# Shifter.net
KiCad netlist of a schematic drawn in Altium Designer
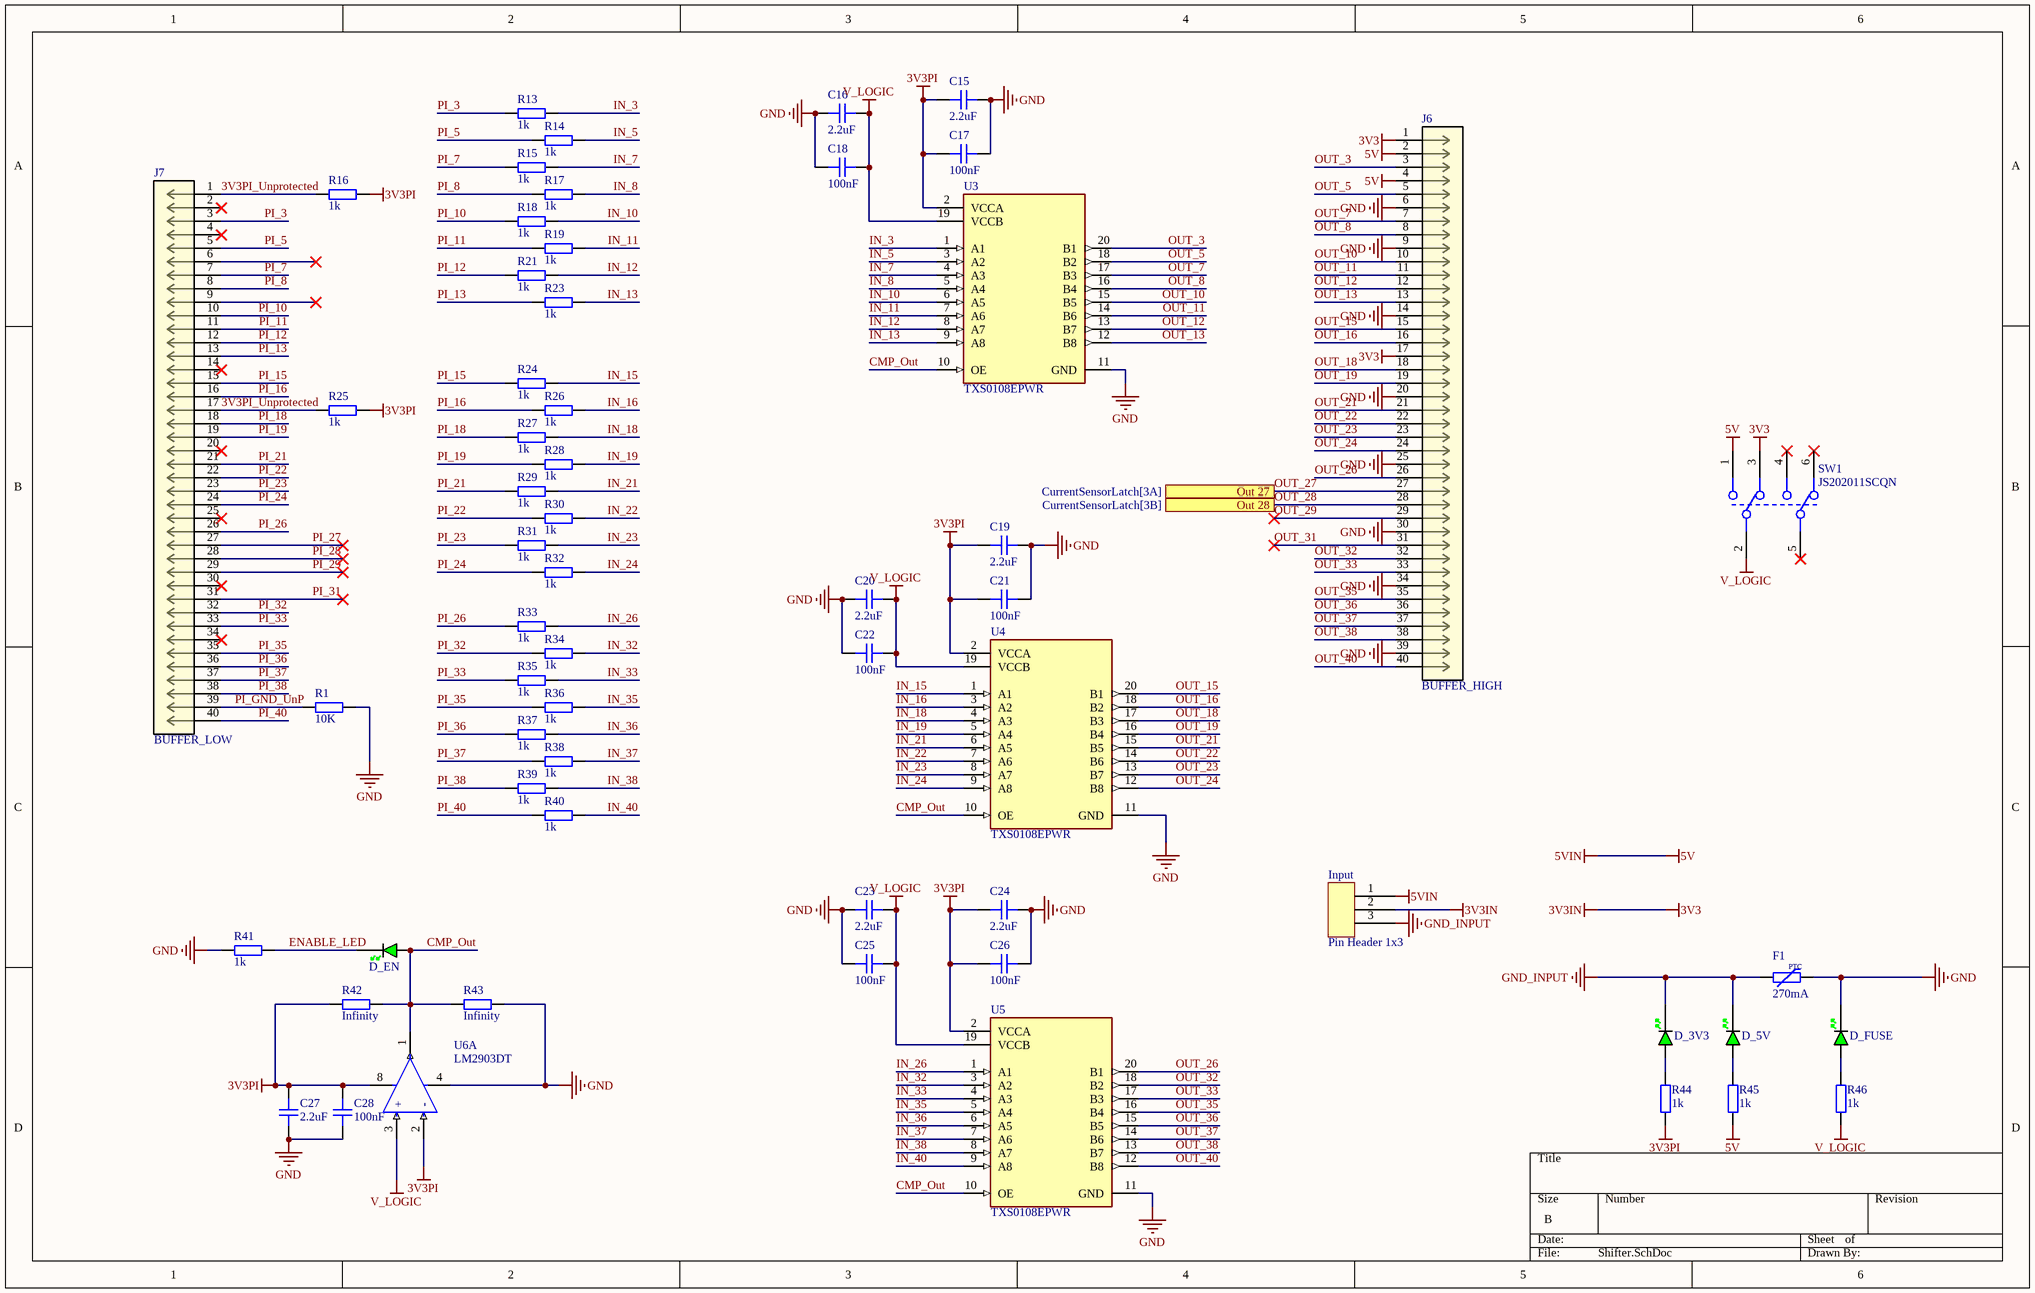
[diagram p0: Shifter.SchDoc]

(export (version "E")
  (design (tool "Eeschema 10.0.6"))
  (components
    (comp (ref "C15")
      (value "2.2uF")
      (footprint "CAP_0805")
      (description "Capacitor SMD 0805 16V")
      (libsource (lib "Schematic-Lib-PhilsLab") (part "CAP_0805_16V"))
    )
    (comp (ref "C16")
      (value "2.2uF")
      (footprint "CAP_0805")
      (description "Capacitor SMD 0805 16V")
      (libsource (lib "Schematic-Lib-PhilsLab") (part "CAP_0805_16V"))
    )
    (comp (ref "C17")
      (value "100nF")
      (footprint "CAP_0805")
      (description "Capacitor SMD 0805 16V")
      (libsource (lib "Schematic-Lib-PhilsLab") (part "CAP_0805_16V"))
    )
    (comp (ref "C18")
      (value "100nF")
      (footprint "CAP_0805")
      (description "Capacitor SMD 0805 16V")
      (libsource (lib "Schematic-Lib-PhilsLab") (part "CAP_0805_16V"))
    )
    (comp (ref "C19")
      (value "2.2uF")
      (footprint "CAP_0805")
      (description "Capacitor SMD 0805 16V")
      (libsource (lib "Schematic-Lib-PhilsLab") (part "CAP_0805_16V"))
    )
    (comp (ref "C20")
      (value "2.2uF")
      (footprint "CAP_0805")
      (description "Capacitor SMD 0805 16V")
      (libsource (lib "Schematic-Lib-PhilsLab") (part "CAP_0805_16V"))
    )
    (comp (ref "C21")
      (value "100nF")
      (footprint "CAP_0805")
      (description "Capacitor SMD 0805 16V")
      (libsource (lib "Schematic-Lib-PhilsLab") (part "CAP_0805_16V"))
    )
    (comp (ref "C22")
      (value "100nF")
      (footprint "CAP_0805")
      (description "Capacitor SMD 0805 16V")
      (libsource (lib "Schematic-Lib-PhilsLab") (part "CAP_0805_16V"))
    )
    (comp (ref "C23")
      (value "2.2uF")
      (footprint "CAP_0805")
      (description "Capacitor SMD 0805 16V")
      (libsource (lib "Schematic-Lib-PhilsLab") (part "CAP_0805_16V"))
    )
    (comp (ref "C24")
      (value "2.2uF")
      (footprint "CAP_0805")
      (description "Capacitor SMD 0805 16V")
      (libsource (lib "Schematic-Lib-PhilsLab") (part "CAP_0805_16V"))
    )
    (comp (ref "C25")
      (value "100nF")
      (footprint "CAP_0805")
      (description "Capacitor SMD 0805 16V")
      (libsource (lib "Schematic-Lib-PhilsLab") (part "CAP_0805_16V"))
    )
    (comp (ref "C26")
      (value "100nF")
      (footprint "CAP_0805")
      (description "Capacitor SMD 0805 16V")
      (libsource (lib "Schematic-Lib-PhilsLab") (part "CAP_0805_16V"))
    )
    (comp (ref "C27")
      (value "2.2uF")
      (footprint "CAP_0805")
      (description "Capacitor SMD 0805 16V")
      (libsource (lib "Schematic-Lib-PhilsLab") (part "CAP_0805_16V"))
    )
    (comp (ref "C28")
      (value "100nF")
      (footprint "CAP_0805")
      (description "Capacitor SMD 0805 16V")
      (libsource (lib "Schematic-Lib-PhilsLab") (part "CAP_0805_16V"))
    )
    (comp (ref "D_3V3")
      (value "GREEN")
      (footprint "LED_0603_GREEN")
      (description "LED 0603 GREEN SMD")
      (libsource (lib "Schematic-Lib-PhilsLab") (part "LED_0603_GREEN"))
    )
    (comp (ref "D_5V")
      (value "GREEN")
      (footprint "LED_0603_GREEN")
      (description "LED 0603 GREEN SMD")
      (libsource (lib "Schematic-Lib-PhilsLab") (part "LED_0603_GREEN"))
    )
    (comp (ref "D_EN")
      (value "GREEN")
      (footprint "LED_0603_GREEN")
      (description "LED 0603 GREEN SMD")
      (libsource (lib "Schematic-Lib-PhilsLab") (part "LED_0603_GREEN"))
    )
    (comp (ref "D_FUSE")
      (value "GREEN")
      (footprint "LED_0603_GREEN")
      (description "LED 0603 GREEN SMD")
      (libsource (lib "Schematic-Lib-PhilsLab") (part "LED_0603_GREEN"))
    )
    (comp (ref "F1")
      (value "270mA")
      (footprint "FUSE_1206")
      (description "Fuse PPTC SMD 1206\r\nSMD1206B010TF")
      (libsource (lib "Schematic-Lib-PhilsLab") (part "FUSE_PPTC_1206"))
    )
    (comp (ref "Input")
      (value "Pin Header 1x3")
      (footprint "Pin Header 1x3")
      (description ".1\" pitch pin header")
      (libsource (lib "TomDownesLibray") (part "Pin Header 1x3"))
    )
    (comp (ref "J6")
      (value "BUFFER_HIGH")
      (footprint "CONN_3020-40-0100-00_CNC")
      (description "No Description Available")
      (libsource (lib "3020-40-0100-00") (part "3020-40-0100-00"))
    )
    (comp (ref "J7")
      (value "BUFFER_LOW")
      (footprint "CONN_3020-40-0100-00_CNC")
      (description "No Description Available")
      (libsource (lib "3020-40-0100-00") (part "3020-40-0100-00"))
    )
    (comp (ref "R1")
      (value "10K")
      (footprint "RES_0603")
      (description "Resistor SMD 0603")
      (libsource (lib "Schematic-Lib-PhilsLab") (part "RES_0603"))
    )
    (comp (ref "R13")
      (value "1k")
      (footprint "RES_0603")
      (description "Resistor SMD 0603")
      (libsource (lib "Schematic-Lib-PhilsLab") (part "RES_0603"))
    )
    (comp (ref "R14")
      (value "1k")
      (footprint "RES_0603")
      (description "Resistor SMD 0603")
      (libsource (lib "Schematic-Lib-PhilsLab") (part "RES_0603"))
    )
    (comp (ref "R15")
      (value "1k")
      (footprint "RES_0603")
      (description "Resistor SMD 0603")
      (libsource (lib "Schematic-Lib-PhilsLab") (part "RES_0603"))
    )
    (comp (ref "R16")
      (value "1k")
      (footprint "RES_0603")
      (description "Resistor SMD 0603")
      (libsource (lib "Schematic-Lib-PhilsLab") (part "RES_0603"))
    )
    (comp (ref "R17")
      (value "1k")
      (footprint "RES_0603")
      (description "Resistor SMD 0603")
      (libsource (lib "Schematic-Lib-PhilsLab") (part "RES_0603"))
    )
    (comp (ref "R18")
      (value "1k")
      (footprint "RES_0603")
      (description "Resistor SMD 0603")
      (libsource (lib "Schematic-Lib-PhilsLab") (part "RES_0603"))
    )
    (comp (ref "R19")
      (value "1k")
      (footprint "RES_0603")
      (description "Resistor SMD 0603")
      (libsource (lib "Schematic-Lib-PhilsLab") (part "RES_0603"))
    )
    (comp (ref "R21")
      (value "1k")
      (footprint "RES_0603")
      (description "Resistor SMD 0603")
      (libsource (lib "Schematic-Lib-PhilsLab") (part "RES_0603"))
    )
    (comp (ref "R23")
      (value "1k")
      (footprint "RES_0603")
      (description "Resistor SMD 0603")
      (libsource (lib "Schematic-Lib-PhilsLab") (part "RES_0603"))
    )
    (comp (ref "R24")
      (value "1k")
      (footprint "RES_0603")
      (description "Resistor SMD 0603")
      (libsource (lib "Schematic-Lib-PhilsLab") (part "RES_0603"))
    )
    (comp (ref "R25")
      (value "1k")
      (footprint "RES_0603")
      (description "Resistor SMD 0603")
      (libsource (lib "Schematic-Lib-PhilsLab") (part "RES_0603"))
    )
    (comp (ref "R26")
      (value "1k")
      (footprint "RES_0603")
      (description "Resistor SMD 0603")
      (libsource (lib "Schematic-Lib-PhilsLab") (part "RES_0603"))
    )
    (comp (ref "R27")
      (value "1k")
      (footprint "RES_0603")
      (description "Resistor SMD 0603")
      (libsource (lib "Schematic-Lib-PhilsLab") (part "RES_0603"))
    )
    (comp (ref "R28")
      (value "1k")
      (footprint "RES_0603")
      (description "Resistor SMD 0603")
      (libsource (lib "Schematic-Lib-PhilsLab") (part "RES_0603"))
    )
    (comp (ref "R29")
      (value "1k")
      (footprint "RES_0603")
      (description "Resistor SMD 0603")
      (libsource (lib "Schematic-Lib-PhilsLab") (part "RES_0603"))
    )
    (comp (ref "R30")
      (value "1k")
      (footprint "RES_0603")
      (description "Resistor SMD 0603")
      (libsource (lib "Schematic-Lib-PhilsLab") (part "RES_0603"))
    )
    (comp (ref "R31")
      (value "1k")
      (footprint "RES_0603")
      (description "Resistor SMD 0603")
      (libsource (lib "Schematic-Lib-PhilsLab") (part "RES_0603"))
    )
    (comp (ref "R32")
      (value "1k")
      (footprint "RES_0603")
      (description "Resistor SMD 0603")
      (libsource (lib "Schematic-Lib-PhilsLab") (part "RES_0603"))
    )
    (comp (ref "R33")
      (value "1k")
      (footprint "RES_0603")
      (description "Resistor SMD 0603")
      (libsource (lib "Schematic-Lib-PhilsLab") (part "RES_0603"))
    )
    (comp (ref "R34")
      (value "1k")
      (footprint "RES_0603")
      (description "Resistor SMD 0603")
      (libsource (lib "Schematic-Lib-PhilsLab") (part "RES_0603"))
    )
    (comp (ref "R35")
      (value "1k")
      (footprint "RES_0603")
      (description "Resistor SMD 0603")
      (libsource (lib "Schematic-Lib-PhilsLab") (part "RES_0603"))
    )
    (comp (ref "R36")
      (value "1k")
      (footprint "RES_0603")
      (description "Resistor SMD 0603")
      (libsource (lib "Schematic-Lib-PhilsLab") (part "RES_0603"))
    )
    (comp (ref "R37")
      (value "1k")
      (footprint "RES_0603")
      (description "Resistor SMD 0603")
      (libsource (lib "Schematic-Lib-PhilsLab") (part "RES_0603"))
    )
    (comp (ref "R38")
      (value "1k")
      (footprint "RES_0603")
      (description "Resistor SMD 0603")
      (libsource (lib "Schematic-Lib-PhilsLab") (part "RES_0603"))
    )
    (comp (ref "R39")
      (value "1k")
      (footprint "RES_0603")
      (description "Resistor SMD 0603")
      (libsource (lib "Schematic-Lib-PhilsLab") (part "RES_0603"))
    )
    (comp (ref "R40")
      (value "1k")
      (footprint "RES_0603")
      (description "Resistor SMD 0603")
      (libsource (lib "Schematic-Lib-PhilsLab") (part "RES_0603"))
    )
    (comp (ref "R41")
      (value "1k")
      (footprint "RES_0603")
      (description "Resistor SMD 0603")
      (libsource (lib "Schematic-Lib-PhilsLab") (part "RES_0603"))
    )
    (comp (ref "R42")
      (value "Infinity")
      (footprint "RES_0603")
      (description "Resistor SMD 0603")
      (libsource (lib "Schematic-Lib-PhilsLab") (part "RES_0603"))
    )
    (comp (ref "R43")
      (value "Infinity")
      (footprint "RES_0603")
      (description "Resistor SMD 0603")
      (libsource (lib "Schematic-Lib-PhilsLab") (part "RES_0603"))
    )
    (comp (ref "R44")
      (value "1k")
      (footprint "RES_0603")
      (description "Resistor SMD 0603")
      (libsource (lib "Schematic-Lib-PhilsLab") (part "RES_0603"))
    )
    (comp (ref "R45")
      (value "1k")
      (footprint "RES_0603")
      (description "Resistor SMD 0603")
      (libsource (lib "Schematic-Lib-PhilsLab") (part "RES_0603"))
    )
    (comp (ref "R46")
      (value "1k")
      (footprint "RES_0603")
      (description "Resistor SMD 0603")
      (libsource (lib "Schematic-Lib-PhilsLab") (part "RES_0603"))
    )
    (comp (ref "SW1")
      (value "JS202011SCQN")
      (footprint "FP-JS202011SCQN-MFG")
      (description "SWITCH SLIDE DPDT 300MA 6V")
      (libsource (lib "Altium Content Vault") (part "ac99ea1af431c19115f5225061c5c88"))
    )
    (comp (ref "U3")
      (value "TXS0108EPWR")
      (footprint "FP-PW0020A-IPC_C")
      (description "IC TRNSLTR BIDIRECTIONAL 20TSSOP")
      (libsource (lib "Altium Content Vault") (part "86128ddf5852d4e934b2dd0188c13f1"))
    )
    (comp (ref "U4")
      (value "TXS0108EPWR")
      (footprint "FP-PW0020A-IPC_C")
      (description "IC TRNSLTR BIDIRECTIONAL 20TSSOP")
      (libsource (lib "Altium Content Vault") (part "86128ddf5852d4e934b2dd0188c13f1"))
    )
    (comp (ref "U5")
      (value "TXS0108EPWR")
      (footprint "FP-PW0020A-IPC_C")
      (description "IC TRNSLTR BIDIRECTIONAL 20TSSOP")
      (libsource (lib "Altium Content Vault") (part "86128ddf5852d4e934b2dd0188c13f1"))
    )
    (comp (ref "U6")
      (value "LM2903DT")
      (footprint "FP-SO8-SO-A-MFG")
      (description "IC COMPARATOR LP DUAL 8-SOIC")
      (fields
        (field (name "MANUFACTURER") "STMicroelectronics")
        (field (name "OCTOPART") "https://octopart.com/lm2903dt-stmicroelectronics-428473")
      )
      (libsource (lib "Altium Content Vault") (part "9f386d5a0a155305257da89b0c2f71e"))
    )
  )
  (nets
    (net (code "1") (name "/3V3PI_Unprotected") (class "Default")
      (node (ref "J7") (pin "1") (pinfunction "1_1") (pintype "passive"))
      (node (ref "J7") (pin "17") (pinfunction "17_17") (pintype "passive"))
      (node (ref "R16") (pin "1") (pinfunction "1_1") (pintype "passive"))
      (node (ref "R25") (pin "1") (pinfunction "1_1") (pintype "passive"))
    )
    (net (code "2") (name "/CMP_Out") (class "Default")
      (node (ref "D_EN") (pin "A") (pinfunction "A_A") (pintype "passive"))
      (node (ref "R42") (pin "2") (pinfunction "2_2") (pintype "passive"))
      (node (ref "R43") (pin "1") (pinfunction "1_1") (pintype "passive"))
      (node (ref "U3") (pin "10") (pinfunction "OE_10") (pintype "input"))
      (node (ref "U4") (pin "10") (pinfunction "OE_10") (pintype "input"))
      (node (ref "U5") (pin "10") (pinfunction "OE_10") (pintype "input"))
      (node (ref "U6") (pin "1") (pinfunction "Out1_1") (pintype "output"))
    )
    (net (code "3") (name "/ENABLE_LED") (class "Default")
      (node (ref "D_EN") (pin "K") (pinfunction "K_K") (pintype "passive"))
      (node (ref "R41") (pin "2") (pinfunction "2_2") (pintype "passive"))
    )
    (net (code "4") (name "/IN_3") (class "Default")
      (node (ref "R13") (pin "2") (pinfunction "2_2") (pintype "passive"))
      (node (ref "U3") (pin "1") (pinfunction "A1_1") (pintype "input"))
    )
    (net (code "5") (name "/IN_5") (class "Default")
      (node (ref "R14") (pin "2") (pinfunction "2_2") (pintype "passive"))
      (node (ref "U3") (pin "3") (pinfunction "A2_3") (pintype "input"))
    )
    (net (code "6") (name "/IN_7") (class "Default")
      (node (ref "R15") (pin "2") (pinfunction "2_2") (pintype "passive"))
      (node (ref "U3") (pin "4") (pinfunction "A3_4") (pintype "input"))
    )
    (net (code "7") (name "/IN_8") (class "Default")
      (node (ref "R17") (pin "2") (pinfunction "2_2") (pintype "passive"))
      (node (ref "U3") (pin "5") (pinfunction "A4_5") (pintype "input"))
    )
    (net (code "8") (name "/IN_10") (class "Default")
      (node (ref "R18") (pin "2") (pinfunction "2_2") (pintype "passive"))
      (node (ref "U3") (pin "6") (pinfunction "A5_6") (pintype "input"))
    )
    (net (code "9") (name "/IN_11") (class "Default")
      (node (ref "R19") (pin "2") (pinfunction "2_2") (pintype "passive"))
      (node (ref "U3") (pin "7") (pinfunction "A6_7") (pintype "input"))
    )
    (net (code "10") (name "/IN_12") (class "Default")
      (node (ref "R21") (pin "2") (pinfunction "2_2") (pintype "passive"))
      (node (ref "U3") (pin "8") (pinfunction "A7_8") (pintype "input"))
    )
    (net (code "11") (name "/IN_13") (class "Default")
      (node (ref "R23") (pin "2") (pinfunction "2_2") (pintype "passive"))
      (node (ref "U3") (pin "9") (pinfunction "A8_9") (pintype "input"))
    )
    (net (code "12") (name "/IN_15") (class "Default")
      (node (ref "R24") (pin "2") (pinfunction "2_2") (pintype "passive"))
      (node (ref "U4") (pin "1") (pinfunction "A1_1") (pintype "input"))
    )
    (net (code "13") (name "/IN_16") (class "Default")
      (node (ref "R26") (pin "2") (pinfunction "2_2") (pintype "passive"))
      (node (ref "U4") (pin "3") (pinfunction "A2_3") (pintype "input"))
    )
    (net (code "14") (name "/IN_18") (class "Default")
      (node (ref "R27") (pin "2") (pinfunction "2_2") (pintype "passive"))
      (node (ref "U4") (pin "4") (pinfunction "A3_4") (pintype "input"))
    )
    (net (code "15") (name "/IN_19") (class "Default")
      (node (ref "R28") (pin "2") (pinfunction "2_2") (pintype "passive"))
      (node (ref "U4") (pin "5") (pinfunction "A4_5") (pintype "input"))
    )
    (net (code "16") (name "/IN_21") (class "Default")
      (node (ref "R29") (pin "2") (pinfunction "2_2") (pintype "passive"))
      (node (ref "U4") (pin "6") (pinfunction "A5_6") (pintype "input"))
    )
    (net (code "17") (name "/IN_22") (class "Default")
      (node (ref "R30") (pin "2") (pinfunction "2_2") (pintype "passive"))
      (node (ref "U4") (pin "7") (pinfunction "A6_7") (pintype "input"))
    )
    (net (code "18") (name "/IN_23") (class "Default")
      (node (ref "R31") (pin "2") (pinfunction "2_2") (pintype "passive"))
      (node (ref "U4") (pin "8") (pinfunction "A7_8") (pintype "input"))
    )
    (net (code "19") (name "/IN_24") (class "Default")
      (node (ref "R32") (pin "2") (pinfunction "2_2") (pintype "passive"))
      (node (ref "U4") (pin "9") (pinfunction "A8_9") (pintype "input"))
    )
    (net (code "20") (name "/IN_26") (class "Default")
      (node (ref "R33") (pin "2") (pinfunction "2_2") (pintype "passive"))
      (node (ref "U5") (pin "1") (pinfunction "A1_1") (pintype "input"))
    )
    (net (code "21") (name "/IN_32") (class "Default")
      (node (ref "R34") (pin "2") (pinfunction "2_2") (pintype "passive"))
      (node (ref "U5") (pin "3") (pinfunction "A2_3") (pintype "input"))
    )
    (net (code "22") (name "/IN_33") (class "Default")
      (node (ref "R35") (pin "2") (pinfunction "2_2") (pintype "passive"))
      (node (ref "U5") (pin "4") (pinfunction "A3_4") (pintype "input"))
    )
    (net (code "23") (name "/IN_35") (class "Default")
      (node (ref "R36") (pin "2") (pinfunction "2_2") (pintype "passive"))
      (node (ref "U5") (pin "5") (pinfunction "A4_5") (pintype "input"))
    )
    (net (code "24") (name "/IN_36") (class "Default")
      (node (ref "R37") (pin "2") (pinfunction "2_2") (pintype "passive"))
      (node (ref "U5") (pin "6") (pinfunction "A5_6") (pintype "input"))
    )
    (net (code "25") (name "/IN_37") (class "Default")
      (node (ref "R38") (pin "2") (pinfunction "2_2") (pintype "passive"))
      (node (ref "U5") (pin "7") (pinfunction "A6_7") (pintype "input"))
    )
    (net (code "26") (name "/IN_38") (class "Default")
      (node (ref "R39") (pin "2") (pinfunction "2_2") (pintype "passive"))
      (node (ref "U5") (pin "8") (pinfunction "A7_8") (pintype "input"))
    )
    (net (code "27") (name "/IN_40") (class "Default")
      (node (ref "R40") (pin "2") (pinfunction "2_2") (pintype "passive"))
      (node (ref "U5") (pin "9") (pinfunction "A8_9") (pintype "input"))
    )
    (net (code "28") (name "/OUT_3") (class "Default")
      (node (ref "J6") (pin "3") (pinfunction "3_3") (pintype "passive"))
      (node (ref "U3") (pin "20") (pinfunction "B1_20") (pintype "output"))
    )
    (net (code "29") (name "/OUT_5") (class "Default")
      (node (ref "J6") (pin "5") (pinfunction "5_5") (pintype "passive"))
      (node (ref "U3") (pin "18") (pinfunction "B2_18") (pintype "output"))
    )
    (net (code "30") (name "/OUT_7") (class "Default")
      (node (ref "J6") (pin "7") (pinfunction "7_7") (pintype "passive"))
      (node (ref "U3") (pin "17") (pinfunction "B3_17") (pintype "output"))
    )
    (net (code "31") (name "/OUT_8") (class "Default")
      (node (ref "J6") (pin "8") (pinfunction "8_8") (pintype "passive"))
      (node (ref "U3") (pin "16") (pinfunction "B4_16") (pintype "output"))
    )
    (net (code "32") (name "/OUT_10") (class "Default")
      (node (ref "J6") (pin "10") (pinfunction "10_10") (pintype "passive"))
      (node (ref "U3") (pin "15") (pinfunction "B5_15") (pintype "output"))
    )
    (net (code "33") (name "/OUT_11") (class "Default")
      (node (ref "J6") (pin "11") (pinfunction "11_11") (pintype "passive"))
      (node (ref "U3") (pin "14") (pinfunction "B6_14") (pintype "output"))
    )
    (net (code "34") (name "/OUT_12") (class "Default")
      (node (ref "J6") (pin "12") (pinfunction "12_12") (pintype "passive"))
      (node (ref "U3") (pin "13") (pinfunction "B7_13") (pintype "output"))
    )
    (net (code "35") (name "/OUT_13") (class "Default")
      (node (ref "J6") (pin "13") (pinfunction "13_13") (pintype "passive"))
      (node (ref "U3") (pin "12") (pinfunction "B8_12") (pintype "output"))
    )
    (net (code "36") (name "/OUT_15") (class "Default")
      (node (ref "J6") (pin "15") (pinfunction "15_15") (pintype "passive"))
      (node (ref "U4") (pin "20") (pinfunction "B1_20") (pintype "output"))
    )
    (net (code "37") (name "/OUT_16") (class "Default")
      (node (ref "J6") (pin "16") (pinfunction "16_16") (pintype "passive"))
      (node (ref "U4") (pin "18") (pinfunction "B2_18") (pintype "output"))
    )
    (net (code "38") (name "/OUT_18") (class "Default")
      (node (ref "J6") (pin "18") (pinfunction "18_18") (pintype "passive"))
      (node (ref "U4") (pin "17") (pinfunction "B3_17") (pintype "output"))
    )
    (net (code "39") (name "/OUT_19") (class "Default")
      (node (ref "J6") (pin "19") (pinfunction "19_19") (pintype "passive"))
      (node (ref "U4") (pin "16") (pinfunction "B4_16") (pintype "output"))
    )
    (net (code "40") (name "/OUT_21") (class "Default")
      (node (ref "J6") (pin "21") (pinfunction "21_21") (pintype "passive"))
      (node (ref "U4") (pin "15") (pinfunction "B5_15") (pintype "output"))
    )
    (net (code "41") (name "/OUT_22") (class "Default")
      (node (ref "J6") (pin "22") (pinfunction "22_22") (pintype "passive"))
      (node (ref "U4") (pin "14") (pinfunction "B6_14") (pintype "output"))
    )
    (net (code "42") (name "/OUT_23") (class "Default")
      (node (ref "J6") (pin "23") (pinfunction "23_23") (pintype "passive"))
      (node (ref "U4") (pin "13") (pinfunction "B7_13") (pintype "output"))
    )
    (net (code "43") (name "/OUT_24") (class "Default")
      (node (ref "J6") (pin "24") (pinfunction "24_24") (pintype "passive"))
      (node (ref "U4") (pin "12") (pinfunction "B8_12") (pintype "output"))
    )
    (net (code "44") (name "/OUT_26") (class "Default")
      (node (ref "J6") (pin "26") (pinfunction "26_26") (pintype "passive"))
      (node (ref "U5") (pin "20") (pinfunction "B1_20") (pintype "output"))
    )
    (net (code "45") (name "/OUT_27") (class "Default")
      (node (ref "J6") (pin "27") (pinfunction "27_27") (pintype "passive"))
    )
    (net (code "46") (name "/OUT_28") (class "Default")
      (node (ref "J6") (pin "28") (pinfunction "28_28") (pintype "passive"))
    )
    (net (code "47") (name "/OUT_29") (class "Default")
      (node (ref "J6") (pin "29") (pinfunction "29_29") (pintype "passive+no_connect"))
    )
    (net (code "48") (name "/OUT_31") (class "Default")
      (node (ref "J6") (pin "31") (pinfunction "31_31") (pintype "passive+no_connect"))
    )
    (net (code "49") (name "/OUT_32") (class "Default")
      (node (ref "J6") (pin "32") (pinfunction "32_32") (pintype "passive"))
      (node (ref "U5") (pin "18") (pinfunction "B2_18") (pintype "output"))
    )
    (net (code "50") (name "/OUT_33") (class "Default")
      (node (ref "J6") (pin "33") (pinfunction "33_33") (pintype "passive"))
      (node (ref "U5") (pin "17") (pinfunction "B3_17") (pintype "output"))
    )
    (net (code "51") (name "/OUT_35") (class "Default")
      (node (ref "J6") (pin "35") (pinfunction "35_35") (pintype "passive"))
      (node (ref "U5") (pin "16") (pinfunction "B4_16") (pintype "output"))
    )
    (net (code "52") (name "/OUT_36") (class "Default")
      (node (ref "J6") (pin "36") (pinfunction "36_36") (pintype "passive"))
      (node (ref "U5") (pin "15") (pinfunction "B5_15") (pintype "output"))
    )
    (net (code "53") (name "/OUT_37") (class "Default")
      (node (ref "J6") (pin "37") (pinfunction "37_37") (pintype "passive"))
      (node (ref "U5") (pin "14") (pinfunction "B6_14") (pintype "output"))
    )
    (net (code "54") (name "/OUT_38") (class "Default")
      (node (ref "J6") (pin "38") (pinfunction "38_38") (pintype "passive"))
      (node (ref "U5") (pin "13") (pinfunction "B7_13") (pintype "output"))
    )
    (net (code "55") (name "/OUT_40") (class "Default")
      (node (ref "J6") (pin "40") (pinfunction "40_40") (pintype "passive"))
      (node (ref "U5") (pin "12") (pinfunction "B8_12") (pintype "output"))
    )
    (net (code "56") (name "/PI_3") (class "Default")
      (node (ref "J7") (pin "3") (pinfunction "3_3") (pintype "passive"))
      (node (ref "R13") (pin "1") (pinfunction "1_1") (pintype "passive"))
    )
    (net (code "57") (name "/PI_5") (class "Default")
      (node (ref "J7") (pin "5") (pinfunction "5_5") (pintype "passive"))
      (node (ref "R14") (pin "1") (pinfunction "1_1") (pintype "passive"))
    )
    (net (code "58") (name "/PI_7") (class "Default")
      (node (ref "J7") (pin "7") (pinfunction "7_7") (pintype "passive"))
      (node (ref "R15") (pin "1") (pinfunction "1_1") (pintype "passive"))
    )
    (net (code "59") (name "/PI_8") (class "Default")
      (node (ref "J7") (pin "8") (pinfunction "8_8") (pintype "passive"))
      (node (ref "R17") (pin "1") (pinfunction "1_1") (pintype "passive"))
    )
    (net (code "60") (name "/PI_10") (class "Default")
      (node (ref "J7") (pin "10") (pinfunction "10_10") (pintype "passive"))
      (node (ref "R18") (pin "1") (pinfunction "1_1") (pintype "passive"))
    )
    (net (code "61") (name "/PI_11") (class "Default")
      (node (ref "J7") (pin "11") (pinfunction "11_11") (pintype "passive"))
      (node (ref "R19") (pin "1") (pinfunction "1_1") (pintype "passive"))
    )
    (net (code "62") (name "/PI_12") (class "Default")
      (node (ref "J7") (pin "12") (pinfunction "12_12") (pintype "passive"))
      (node (ref "R21") (pin "1") (pinfunction "1_1") (pintype "passive"))
    )
    (net (code "63") (name "/PI_13") (class "Default")
      (node (ref "J7") (pin "13") (pinfunction "13_13") (pintype "passive"))
      (node (ref "R23") (pin "1") (pinfunction "1_1") (pintype "passive"))
    )
    (net (code "64") (name "/PI_15") (class "Default")
      (node (ref "J7") (pin "15") (pinfunction "15_15") (pintype "passive"))
      (node (ref "R24") (pin "1") (pinfunction "1_1") (pintype "passive"))
    )
    (net (code "65") (name "/PI_16") (class "Default")
      (node (ref "J7") (pin "16") (pinfunction "16_16") (pintype "passive"))
      (node (ref "R26") (pin "1") (pinfunction "1_1") (pintype "passive"))
    )
    (net (code "66") (name "/PI_18") (class "Default")
      (node (ref "J7") (pin "18") (pinfunction "18_18") (pintype "passive"))
      (node (ref "R27") (pin "1") (pinfunction "1_1") (pintype "passive"))
    )
    (net (code "67") (name "/PI_19") (class "Default")
      (node (ref "J7") (pin "19") (pinfunction "19_19") (pintype "passive"))
      (node (ref "R28") (pin "1") (pinfunction "1_1") (pintype "passive"))
    )
    (net (code "68") (name "/PI_21") (class "Default")
      (node (ref "J7") (pin "21") (pinfunction "21_21") (pintype "passive"))
      (node (ref "R29") (pin "1") (pinfunction "1_1") (pintype "passive"))
    )
    (net (code "69") (name "/PI_22") (class "Default")
      (node (ref "J7") (pin "22") (pinfunction "22_22") (pintype "passive"))
      (node (ref "R30") (pin "1") (pinfunction "1_1") (pintype "passive"))
    )
    (net (code "70") (name "/PI_23") (class "Default")
      (node (ref "J7") (pin "23") (pinfunction "23_23") (pintype "passive"))
      (node (ref "R31") (pin "1") (pinfunction "1_1") (pintype "passive"))
    )
    (net (code "71") (name "/PI_24") (class "Default")
      (node (ref "J7") (pin "24") (pinfunction "24_24") (pintype "passive"))
      (node (ref "R32") (pin "1") (pinfunction "1_1") (pintype "passive"))
    )
    (net (code "72") (name "/PI_26") (class "Default")
      (node (ref "J7") (pin "26") (pinfunction "26_26") (pintype "passive"))
      (node (ref "R33") (pin "1") (pinfunction "1_1") (pintype "passive"))
    )
    (net (code "73") (name "/PI_27") (class "Default")
      (node (ref "J7") (pin "27") (pinfunction "27_27") (pintype "passive+no_connect"))
    )
    (net (code "74") (name "/PI_28") (class "Default")
      (node (ref "J7") (pin "28") (pinfunction "28_28") (pintype "passive+no_connect"))
    )
    (net (code "75") (name "/PI_29") (class "Default")
      (node (ref "J7") (pin "29") (pinfunction "29_29") (pintype "passive+no_connect"))
    )
    (net (code "76") (name "/PI_31") (class "Default")
      (node (ref "J7") (pin "31") (pinfunction "31_31") (pintype "passive+no_connect"))
    )
    (net (code "77") (name "/PI_32") (class "Default")
      (node (ref "J7") (pin "32") (pinfunction "32_32") (pintype "passive"))
      (node (ref "R34") (pin "1") (pinfunction "1_1") (pintype "passive"))
    )
    (net (code "78") (name "/PI_33") (class "Default")
      (node (ref "J7") (pin "33") (pinfunction "33_33") (pintype "passive"))
      (node (ref "R35") (pin "1") (pinfunction "1_1") (pintype "passive"))
    )
    (net (code "79") (name "/PI_35") (class "Default")
      (node (ref "J7") (pin "35") (pinfunction "35_35") (pintype "passive"))
      (node (ref "R36") (pin "1") (pinfunction "1_1") (pintype "passive"))
    )
    (net (code "80") (name "/PI_36") (class "Default")
      (node (ref "J7") (pin "36") (pinfunction "36_36") (pintype "passive"))
      (node (ref "R37") (pin "1") (pinfunction "1_1") (pintype "passive"))
    )
    (net (code "81") (name "/PI_37") (class "Default")
      (node (ref "J7") (pin "37") (pinfunction "37_37") (pintype "passive"))
      (node (ref "R38") (pin "1") (pinfunction "1_1") (pintype "passive"))
    )
    (net (code "82") (name "/PI_38") (class "Default")
      (node (ref "J7") (pin "38") (pinfunction "38_38") (pintype "passive"))
      (node (ref "R39") (pin "1") (pinfunction "1_1") (pintype "passive"))
    )
    (net (code "83") (name "/PI_40") (class "Default")
      (node (ref "J7") (pin "40") (pinfunction "40_40") (pintype "passive"))
      (node (ref "R40") (pin "1") (pinfunction "1_1") (pintype "passive"))
    )
    (net (code "84") (name "/PI_GND_UnP") (class "Default")
      (node (ref "J7") (pin "39") (pinfunction "39_39") (pintype "passive"))
      (node (ref "R1") (pin "1") (pinfunction "1_1") (pintype "passive"))
    )
    (net (code "85") (name "3V3") (class "Default")
      (node (ref "Input") (pin "2") (pinfunction "2_2") (pintype "passive"))
      (node (ref "J6") (pin "1") (pinfunction "1_1") (pintype "passive"))
      (node (ref "J6") (pin "17") (pinfunction "17_17") (pintype "passive"))
      (node (ref "SW1") (pin "3") (pinfunction "3_3") (pintype "passive"))
    )
    (net (code "86") (name "3V3PI") (class "Default")
      (node (ref "C15") (pin "2") (pinfunction "2_2") (pintype "passive"))
      (node (ref "C17") (pin "2") (pinfunction "2_2") (pintype "passive"))
      (node (ref "C19") (pin "2") (pinfunction "2_2") (pintype "passive"))
      (node (ref "C21") (pin "2") (pinfunction "2_2") (pintype "passive"))
      (node (ref "C24") (pin "2") (pinfunction "2_2") (pintype "passive"))
      (node (ref "C26") (pin "2") (pinfunction "2_2") (pintype "passive"))
      (node (ref "C27") (pin "2") (pinfunction "2_2") (pintype "passive"))
      (node (ref "C28") (pin "1") (pinfunction "1_1") (pintype "passive"))
      (node (ref "R16") (pin "2") (pinfunction "2_2") (pintype "passive"))
      (node (ref "R25") (pin "2") (pinfunction "2_2") (pintype "passive"))
      (node (ref "R42") (pin "1") (pinfunction "1_1") (pintype "passive"))
      (node (ref "R44") (pin "1") (pinfunction "1_1") (pintype "passive"))
      (node (ref "U3") (pin "2") (pinfunction "VCCA_2") (pintype "power_in"))
      (node (ref "U4") (pin "2") (pinfunction "VCCA_2") (pintype "power_in"))
      (node (ref "U5") (pin "2") (pinfunction "VCCA_2") (pintype "power_in"))
      (node (ref "U6") (pin "2") (pinfunction "In1-_2") (pintype "input"))
      (node (ref "U6") (pin "8") (pinfunction "VCC+_8") (pintype "power_in"))
    )
    (net (code "87") (name "5V") (class "Default")
      (node (ref "Input") (pin "1") (pinfunction "1_1") (pintype "passive"))
      (node (ref "J6") (pin "2") (pinfunction "2_2") (pintype "passive"))
      (node (ref "J6") (pin "4") (pinfunction "4_4") (pintype "passive"))
      (node (ref "R45") (pin "1") (pinfunction "1_1") (pintype "passive"))
      (node (ref "SW1") (pin "1") (pinfunction "1_1") (pintype "passive"))
    )
    (net (code "88") (name "GND") (class "Default")
      (node (ref "C15") (pin "1") (pinfunction "1_1") (pintype "passive"))
      (node (ref "C16") (pin "2") (pinfunction "2_2") (pintype "passive"))
      (node (ref "C17") (pin "1") (pinfunction "1_1") (pintype "passive"))
      (node (ref "C18") (pin "2") (pinfunction "2_2") (pintype "passive"))
      (node (ref "C19") (pin "1") (pinfunction "1_1") (pintype "passive"))
      (node (ref "C20") (pin "2") (pinfunction "2_2") (pintype "passive"))
      (node (ref "C21") (pin "1") (pinfunction "1_1") (pintype "passive"))
      (node (ref "C22") (pin "2") (pinfunction "2_2") (pintype "passive"))
      (node (ref "C23") (pin "2") (pinfunction "2_2") (pintype "passive"))
      (node (ref "C24") (pin "1") (pinfunction "1_1") (pintype "passive"))
      (node (ref "C25") (pin "2") (pinfunction "2_2") (pintype "passive"))
      (node (ref "C26") (pin "1") (pinfunction "1_1") (pintype "passive"))
      (node (ref "C27") (pin "1") (pinfunction "1_1") (pintype "passive"))
      (node (ref "C28") (pin "2") (pinfunction "2_2") (pintype "passive"))
      (node (ref "D_FUSE") (pin "K") (pinfunction "K_K") (pintype "passive"))
      (node (ref "F1") (pin "2") (pinfunction "2_2") (pintype "passive"))
      (node (ref "J6") (pin "14") (pinfunction "14_14") (pintype "passive"))
      (node (ref "J6") (pin "20") (pinfunction "20_20") (pintype "passive"))
      (node (ref "J6") (pin "25") (pinfunction "25_25") (pintype "passive"))
      (node (ref "J6") (pin "30") (pinfunction "30_30") (pintype "passive"))
      (node (ref "J6") (pin "34") (pinfunction "34_34") (pintype "passive"))
      (node (ref "J6") (pin "39") (pinfunction "39_39") (pintype "passive"))
      (node (ref "J6") (pin "6") (pinfunction "6_6") (pintype "passive"))
      (node (ref "J6") (pin "9") (pinfunction "9_9") (pintype "passive"))
      (node (ref "R1") (pin "2") (pinfunction "2_2") (pintype "passive"))
      (node (ref "R41") (pin "1") (pinfunction "1_1") (pintype "passive"))
      (node (ref "R43") (pin "2") (pinfunction "2_2") (pintype "passive"))
      (node (ref "U3") (pin "11") (pinfunction "GND_11") (pintype "power_in"))
      (node (ref "U4") (pin "11") (pinfunction "GND_11") (pintype "power_in"))
      (node (ref "U5") (pin "11") (pinfunction "GND_11") (pintype "power_in"))
      (node (ref "U6") (pin "4") (pinfunction "VCC-_4") (pintype "power_in"))
    )
    (net (code "89") (name "GND_INPUT") (class "Default")
      (node (ref "D_3V3") (pin "K") (pinfunction "K_K") (pintype "passive"))
      (node (ref "D_5V") (pin "K") (pinfunction "K_K") (pintype "passive"))
      (node (ref "F1") (pin "1") (pinfunction "1_1") (pintype "passive"))
      (node (ref "Input") (pin "3") (pinfunction "3_3") (pintype "passive"))
    )
    (net (code "90") (name "Net-(D_3V3-PadA)") (class "Default")
      (node (ref "D_3V3") (pin "A") (pinfunction "A_A") (pintype "passive"))
      (node (ref "R44") (pin "2") (pinfunction "2_2") (pintype "passive"))
    )
    (net (code "91") (name "Net-(D_5V-PadA)") (class "Default")
      (node (ref "D_5V") (pin "A") (pinfunction "A_A") (pintype "passive"))
      (node (ref "R45") (pin "2") (pinfunction "2_2") (pintype "passive"))
    )
    (net (code "92") (name "Net-(D_FUSE-PadA)") (class "Default")
      (node (ref "D_FUSE") (pin "A") (pinfunction "A_A") (pintype "passive"))
      (node (ref "R46") (pin "2") (pinfunction "2_2") (pintype "passive"))
    )
    (net (code "93") (name "V_LOGIC") (class "Default")
      (node (ref "C16") (pin "1") (pinfunction "1_1") (pintype "passive"))
      (node (ref "C18") (pin "1") (pinfunction "1_1") (pintype "passive"))
      (node (ref "C20") (pin "1") (pinfunction "1_1") (pintype "passive"))
      (node (ref "C22") (pin "1") (pinfunction "1_1") (pintype "passive"))
      (node (ref "C23") (pin "1") (pinfunction "1_1") (pintype "passive"))
      (node (ref "C25") (pin "1") (pinfunction "1_1") (pintype "passive"))
      (node (ref "R46") (pin "1") (pinfunction "1_1") (pintype "passive"))
      (node (ref "SW1") (pin "2") (pinfunction "2_2") (pintype "passive"))
      (node (ref "U3") (pin "19") (pinfunction "VCCB_19") (pintype "power_in"))
      (node (ref "U4") (pin "19") (pinfunction "VCCB_19") (pintype "power_in"))
      (node (ref "U5") (pin "19") (pinfunction "VCCB_19") (pintype "power_in"))
      (node (ref "U6") (pin "3") (pinfunction "In1+_3") (pintype "input"))
    )
    (net (code "94") (name "unconnected-(J7-Pad2)") (class "Default")
      (node (ref "J7") (pin "2") (pinfunction "2_2") (pintype "passive+no_connect"))
    )
    (net (code "95") (name "unconnected-(J7-Pad4)") (class "Default")
      (node (ref "J7") (pin "4") (pinfunction "4_4") (pintype "passive+no_connect"))
    )
    (net (code "96") (name "unconnected-(J7-Pad6)") (class "Default")
      (node (ref "J7") (pin "6") (pinfunction "6_6") (pintype "passive+no_connect"))
    )
    (net (code "97") (name "unconnected-(J7-Pad9)") (class "Default")
      (node (ref "J7") (pin "9") (pinfunction "9_9") (pintype "passive+no_connect"))
    )
    (net (code "98") (name "unconnected-(J7-Pad14)") (class "Default")
      (node (ref "J7") (pin "14") (pinfunction "14_14") (pintype "passive+no_connect"))
    )
    (net (code "99") (name "unconnected-(J7-Pad20)") (class "Default")
      (node (ref "J7") (pin "20") (pinfunction "20_20") (pintype "passive+no_connect"))
    )
    (net (code "100") (name "unconnected-(J7-Pad25)") (class "Default")
      (node (ref "J7") (pin "25") (pinfunction "25_25") (pintype "passive+no_connect"))
    )
    (net (code "101") (name "unconnected-(J7-Pad30)") (class "Default")
      (node (ref "J7") (pin "30") (pinfunction "30_30") (pintype "passive+no_connect"))
    )
    (net (code "102") (name "unconnected-(J7-Pad34)") (class "Default")
      (node (ref "J7") (pin "34") (pinfunction "34_34") (pintype "passive+no_connect"))
    )
    (net (code "103") (name "unconnected-(SW1-Pad4)") (class "Default")
      (node (ref "SW1") (pin "4") (pinfunction "4_4") (pintype "passive+no_connect"))
    )
    (net (code "104") (name "unconnected-(SW1-Pad5)") (class "Default")
      (node (ref "SW1") (pin "5") (pinfunction "5_5") (pintype "passive+no_connect"))
    )
    (net (code "105") (name "unconnected-(SW1-Pad6)") (class "Default")
      (node (ref "SW1") (pin "6") (pinfunction "6_6") (pintype "passive+no_connect"))
    )
  )
)
